# GPRSshield_v1_4.net
KiCad netlist of a schematic drawn in EAGLE
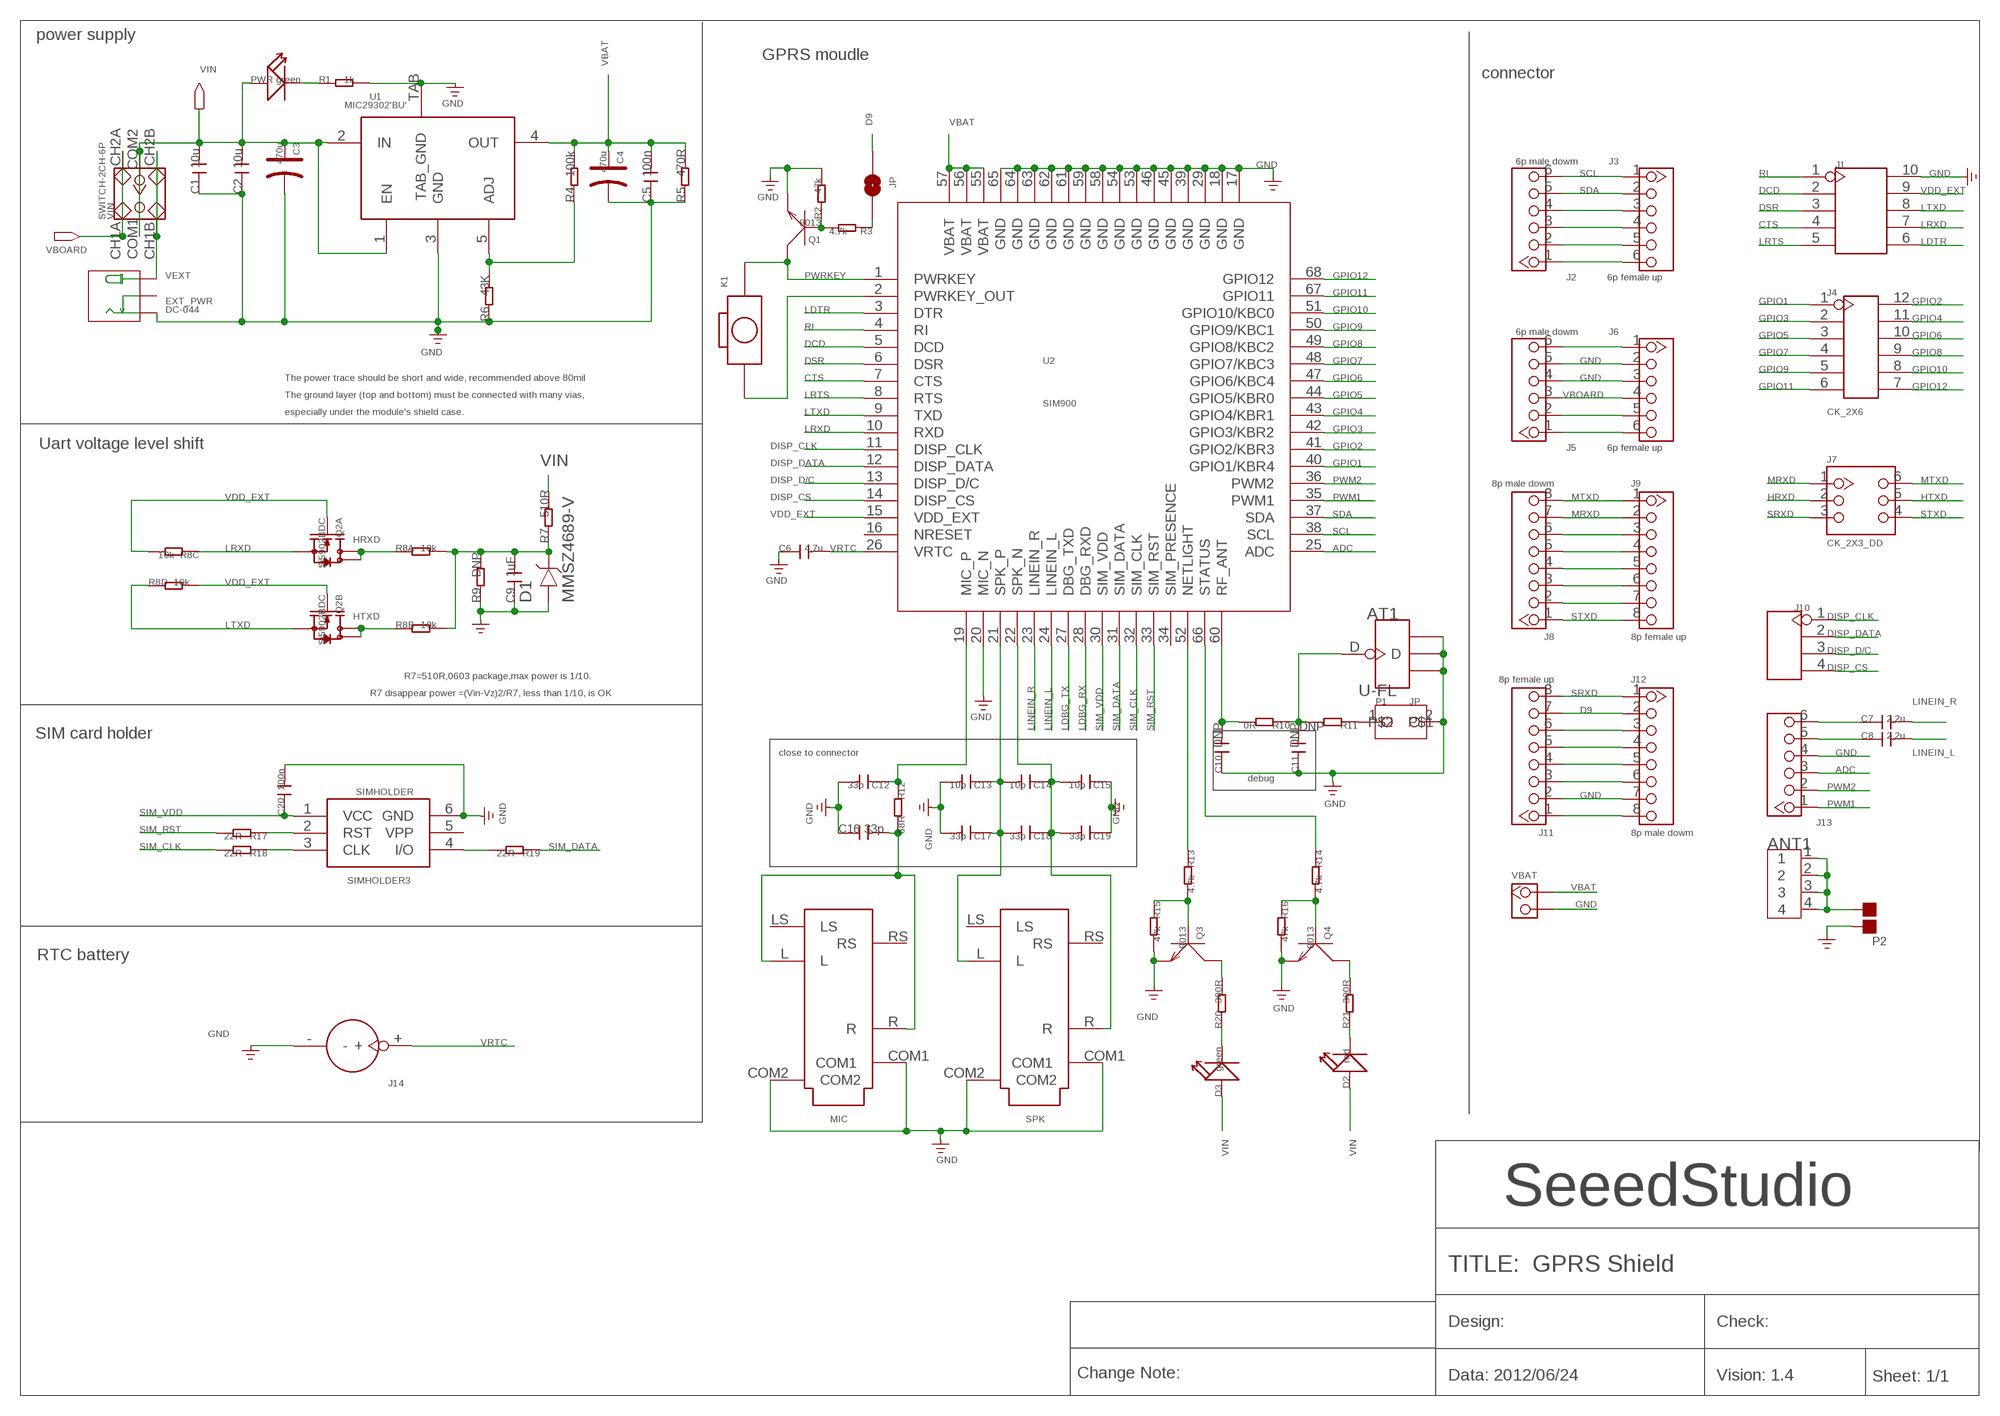
[diagram p0: schematic, sheet 1]

(export (version "E")
  (design (tool "Eeschema 10.0.6"))
  (components
    (comp (ref "ANT1")
      (value "ANTENNA-SMA-IPX")
      (footprint "eagle-import:SMA-TO-IPX")
      (libsource (lib "eagle-import") (part "ANTENNA-SMA-IPX"))
    )
    (comp (ref "AT1")
      (value "U-FL")
      (footprint "eagle-import:4P-U-FL")
      (libsource (lib "eagle-import") (part "ANTENNA-U-FL"))
    )
    (comp (ref "C1")
      (value "10u")
      (footprint "eagle-import:0603")
      (libsource (lib "eagle-import") (part "C-0603"))
    )
    (comp (ref "C2")
      (value "10u")
      (footprint "eagle-import:0603")
      (libsource (lib "eagle-import") (part "C-0603"))
    )
    (comp (ref "C3")
      (value "470u")
      (footprint "eagle-import:AVX_D")
      (libsource (lib "eagle-import") (part "006-CAP_AVX_D"))
    )
    (comp (ref "C4")
      (value "470u")
      (footprint "eagle-import:AVX_D")
      (libsource (lib "eagle-import") (part "006-CAP_AVX_D"))
    )
    (comp (ref "C5")
      (value "100n")
      (footprint "eagle-import:0603")
      (libsource (lib "eagle-import") (part "C-0603"))
    )
    (comp (ref "C6")
      (value "4.7u")
      (footprint "eagle-import:0805")
      (libsource (lib "eagle-import") (part "C-0805"))
    )
    (comp (ref "C7")
      (value "2.2u")
      (footprint "eagle-import:0603")
      (libsource (lib "eagle-import") (part "C-0603"))
    )
    (comp (ref "C8")
      (value "2.2u")
      (footprint "eagle-import:0603")
      (libsource (lib "eagle-import") (part "C-0603"))
    )
    (comp (ref "C9")
      (value "1uF")
      (footprint "eagle-import:0603")
      (libsource (lib "eagle-import") (part "C-0603"))
    )
    (comp (ref "C10")
      (value "DNP")
      (footprint "eagle-import:0402")
      (libsource (lib "eagle-import") (part "C-0402"))
    )
    (comp (ref "C11")
      (value "DNP")
      (footprint "eagle-import:0402")
      (libsource (lib "eagle-import") (part "C-0402"))
    )
    (comp (ref "C12")
      (value "33p")
      (footprint "eagle-import:0603")
      (libsource (lib "eagle-import") (part "C-0603"))
    )
    (comp (ref "C13")
      (value "10p")
      (footprint "eagle-import:0402")
      (libsource (lib "eagle-import") (part "C-0402"))
    )
    (comp (ref "C14")
      (value "10p")
      (footprint "eagle-import:0402")
      (libsource (lib "eagle-import") (part "C-0402"))
    )
    (comp (ref "C15")
      (value "10p")
      (footprint "eagle-import:0402")
      (libsource (lib "eagle-import") (part "C-0402"))
    )
    (comp (ref "C16")
      (value "33p")
      (footprint "eagle-import:0603")
      (libsource (lib "eagle-import") (part "C-0603"))
    )
    (comp (ref "C17")
      (value "33p")
      (footprint "eagle-import:0402")
      (libsource (lib "eagle-import") (part "C-0402"))
    )
    (comp (ref "C18")
      (value "33p")
      (footprint "eagle-import:0402")
      (libsource (lib "eagle-import") (part "C-0402"))
    )
    (comp (ref "C19")
      (value "33p")
      (footprint "eagle-import:0402")
      (libsource (lib "eagle-import") (part "C-0402"))
    )
    (comp (ref "C20")
      (value "100n")
      (footprint "eagle-import:0603")
      (libsource (lib "eagle-import") (part "C-0603"))
    )
    (comp (ref "D1")
      (value "MMSZ4689-V")
      (footprint "eagle-import:SOD123-2.7X1.6")
      (libsource (lib "eagle-import") (part "D-VOL'MMSZ4681'"))
    )
    (comp (ref "D2")
      (value "red")
      (footprint "eagle-import:LED-0603")
      (libsource (lib "eagle-import") (part "LED'0603'"))
    )
    (comp (ref "D3")
      (value "green")
      (footprint "eagle-import:LED-0603")
      (libsource (lib "eagle-import") (part "LED'0603'"))
    )
    (comp (ref "EXT_PWR")
      (value "DC-044")
      (footprint "eagle-import:DC-404")
      (libsource (lib "eagle-import") (part "DC-044"))
    )
    (comp (ref "J1")
      (value "HEADER-2X5P-2.54")
      (footprint "eagle-import:2X5P-2.54")
      (libsource (lib "eagle-import") (part "HEADER-2X5P-2.54"))
    )
    (comp (ref "J2")
      (value "6p male dowm")
      (footprint "eagle-import:CK_1X6")
      (libsource (lib "eagle-import") (part "HEADER_1X6"))
    )
    (comp (ref "J3")
      (value "6p female up")
      (footprint "eagle-import:CK_1X6")
      (libsource (lib "eagle-import") (part "HEADER_1X6"))
    )
    (comp (ref "J4")
      (value "CK_2X6")
      (footprint "eagle-import:CK_2X6")
      (libsource (lib "eagle-import") (part "CK_2X6"))
    )
    (comp (ref "J5")
      (value "6p male dowm")
      (footprint "eagle-import:CK_1X6")
      (libsource (lib "eagle-import") (part "HEADER_1X6"))
    )
    (comp (ref "J6")
      (value "6p female up")
      (footprint "eagle-import:CK_1X6")
      (libsource (lib "eagle-import") (part "HEADER_1X6"))
    )
    (comp (ref "J7")
      (value "CK_2X3_DD")
      (footprint "eagle-import:CK_2X3")
      (libsource (lib "eagle-import") (part "CK_2X3_DD"))
    )
    (comp (ref "J8")
      (value "8p male dowm")
      (footprint "eagle-import:CK_1X8")
      (libsource (lib "eagle-import") (part "CK_1X8DD"))
    )
    (comp (ref "J9")
      (value "8p female up")
      (footprint "eagle-import:CK_1X8")
      (libsource (lib "eagle-import") (part "CK_1X8DD"))
    )
    (comp (ref "J10")
      (value "HEADER-4P'2.54-90D-FEMALE'")
      (footprint "eagle-import:4P-2.54-90D-FEMALE")
      (libsource (lib "eagle-import") (part "HEADER-4P'2.54-90D-FEMALE'"))
    )
    (comp (ref "J11")
      (value "8p female up")
      (footprint "eagle-import:CK_1X8")
      (libsource (lib "eagle-import") (part "CK_1X8DD"))
    )
    (comp (ref "J12")
      (value "8p male dowm")
      (footprint "eagle-import:CK_1X8")
      (libsource (lib "eagle-import") (part "CK_1X8DD"))
    )
    (comp (ref "J13")
      (value "HEADER_1X6")
      (footprint "eagle-import:CK_1X6")
      (libsource (lib "eagle-import") (part "HEADER_1X6"))
    )
    (comp (ref "J14")
      (value "HOLDER-BATTERY-2P-CR1220")
      (footprint "eagle-import:CR1220")
      (libsource (lib "eagle-import") (part "HOLDER-BATTERY-2P-CR1220"))
    )
    (comp (ref "JP")
      (value "PAD-SOLDERJUMPERNC")
      (footprint "eagle-import:2P-SMD-3.3X2")
      (libsource (lib "eagle-import") (part "PAD-SOLDERJUMPERNC"))
    )
    (comp (ref "K1")
      (value "BOTTON_1_DP")
      (footprint "eagle-import:BTN_5.0_RST")
      (libsource (lib "eagle-import") (part "BOTTON_1_DP"))
    )
    (comp (ref "MIC")
      (value "AUDIO-SMT")
      (footprint "eagle-import:3.5-SMD")
      (libsource (lib "eagle-import") (part "AUDIO-SMT"))
    )
    (comp (ref "P1") (value "JP") (footprint "eagle-import:JP") (libsource (lib "eagle-import") (part "JP")))
    (comp (ref "P2")
      (value "PAD-JUMPER-2P")
      (footprint "eagle-import:2P-SMD-1.78X1.27")
      (fields (field (name "PARTNO") "DNP"))
      (libsource (lib "eagle-import") (part "PAD-JUMPER-2P"))
    )
    (comp (ref "PWR")
      (value "green")
      (footprint "eagle-import:D0603")
      (libsource (lib "eagle-import") (part "007-LED0603"))
    )
    (comp (ref "Q1")
      (value "9013")
      (footprint "eagle-import:SOT23")
      (libsource (lib "eagle-import") (part "TRANSISTOR-NPN-SOT23"))
    )
    (comp (ref "Q2")
      (value "Si5902BDC")
      (footprint "eagle-import:1206-8")
      (libsource (lib "eagle-import") (part "010-DUAL-N-MOSFET_1206-8"))
    )
    (comp (ref "Q3")
      (value "9013")
      (footprint "eagle-import:SOT23")
      (libsource (lib "eagle-import") (part "TRANSISTOR-NPN-SOT23"))
    )
    (comp (ref "Q4")
      (value "9013")
      (footprint "eagle-import:SOT23")
      (libsource (lib "eagle-import") (part "TRANSISTOR-NPN-SOT23"))
    )
    (comp (ref "R1")
      (value "1k")
      (footprint "eagle-import:0603")
      (libsource (lib "eagle-import") (part "R-0603"))
    )
    (comp (ref "R2")
      (value "47k")
      (footprint "eagle-import:0603")
      (libsource (lib "eagle-import") (part "R-0603"))
    )
    (comp (ref "R3")
      (value "4.7k")
      (footprint "eagle-import:0603")
      (libsource (lib "eagle-import") (part "R-0603"))
    )
    (comp (ref "R4")
      (value "100k")
      (footprint "eagle-import:0603")
      (libsource (lib "eagle-import") (part "R-0603"))
    )
    (comp (ref "R5")
      (value "470R")
      (footprint "eagle-import:0603")
      (libsource (lib "eagle-import") (part "R-0603"))
    )
    (comp (ref "R6")
      (value "43K")
      (footprint "eagle-import:0603")
      (libsource (lib "eagle-import") (part "R-0603"))
    )
    (comp (ref "R7")
      (value "510R")
      (footprint "eagle-import:0603")
      (libsource (lib "eagle-import") (part "R-0603"))
    )
    (comp (ref "R8")
      (value "10k")
      (footprint "eagle-import:1206-8-3.3X2.4")
      (libsource (lib "eagle-import") (part "R-4R-1206"))
    )
    (comp (ref "R9")
      (value "DNP")
      (footprint "eagle-import:0603")
      (libsource (lib "eagle-import") (part "R-0603"))
    )
    (comp (ref "R10")
      (value "0R")
      (footprint "eagle-import:0402")
      (libsource (lib "eagle-import") (part "R-0402"))
    )
    (comp (ref "R11")
      (value "DNP")
      (footprint "eagle-import:0402")
      (libsource (lib "eagle-import") (part "R-0402"))
    )
    (comp (ref "R12")
      (value "68R")
      (footprint "eagle-import:0603")
      (libsource (lib "eagle-import") (part "R-0603"))
    )
    (comp (ref "R13")
      (value "4.7k")
      (footprint "eagle-import:0603")
      (libsource (lib "eagle-import") (part "R-0603"))
    )
    (comp (ref "R14")
      (value "4.7k")
      (footprint "eagle-import:0603")
      (libsource (lib "eagle-import") (part "R-0603"))
    )
    (comp (ref "R15")
      (value "47k")
      (footprint "eagle-import:0603")
      (libsource (lib "eagle-import") (part "R-0603"))
    )
    (comp (ref "R16")
      (value "47k")
      (footprint "eagle-import:0603")
      (libsource (lib "eagle-import") (part "R-0603"))
    )
    (comp (ref "R17")
      (value "22R")
      (footprint "eagle-import:0603")
      (libsource (lib "eagle-import") (part "R-0603"))
    )
    (comp (ref "R18")
      (value "22R")
      (footprint "eagle-import:0603")
      (libsource (lib "eagle-import") (part "R-0603"))
    )
    (comp (ref "R19")
      (value "22R")
      (footprint "eagle-import:0603")
      (libsource (lib "eagle-import") (part "R-0603"))
    )
    (comp (ref "R20")
      (value "300R")
      (footprint "eagle-import:0603")
      (libsource (lib "eagle-import") (part "R-0603"))
    )
    (comp (ref "R21")
      (value "300R")
      (footprint "eagle-import:0603")
      (libsource (lib "eagle-import") (part "R-0603"))
    )
    (comp (ref "SIMHOLDER")
      (value "SIMHOLDER3")
      (footprint "eagle-import:SIMHOLDER3")
      (libsource (lib "eagle-import") (part "SIMHOLDER3"))
    )
    (comp (ref "SPK")
      (value "AUDIO-SMT")
      (footprint "eagle-import:3.5-SMD")
      (libsource (lib "eagle-import") (part "AUDIO-SMT"))
    )
    (comp (ref "U1")
      (value "MIC29302'BU'")
      (footprint "eagle-import:TO-263")
      (libsource (lib "eagle-import") (part "MIC29302'BU'"))
    )
    (comp (ref "U2")
      (value "SIM900")
      (footprint "eagle-import:SIM900")
      (libsource (lib "eagle-import") (part "SIM900"))
    )
    (comp (ref "VBAT")
      (value "DNP")
      (footprint "eagle-import:CK_1_2")
      (libsource (lib "eagle-import") (part "HEADER_1X2_2.54"))
    )
    (comp (ref "VIN")
      (value "SWITCH-2CH-6P")
      (footprint "eagle-import:6P-2CH-2.54-7.6X3.0")
      (libsource (lib "eagle-import") (part "SWITCH-2CH-6P"))
    )
  )
  (nets
    (net (code "1") (name "/ADC") (class "Default")
      (node (ref "J13") (pin "3") (pinfunction "3_3") (pintype "bidirectional"))
      (node (ref "U2") (pin "25") (pinfunction "ADC_25") (pintype "input"))
    )
    (net (code "2") (name "/CTS") (class "Default")
      (node (ref "J1") (pin "4") (pinfunction "4_4") (pintype "bidirectional"))
      (node (ref "U2") (pin "7") (pinfunction "CTS_7") (pintype "output"))
    )
    (net (code "3") (name "/D9") (class "Default")
      (node (ref "J11") (pin "7") (pinfunction "P$7_7") (pintype "bidirectional"))
      (node (ref "J12") (pin "2") (pinfunction "P$2_2") (pintype "bidirectional"))
      (node (ref "JP") (pin "1") (pinfunction "1_1") (pintype "passive"))
    )
    (net (code "4") (name "/DCD") (class "Default")
      (node (ref "J1") (pin "2") (pinfunction "2_2") (pintype "bidirectional"))
      (node (ref "U2") (pin "5") (pinfunction "DCD_5") (pintype "output"))
    )
    (net (code "5") (name "/DISP_CLK") (class "Default")
      (node (ref "J10") (pin "1") (pinfunction "P$1_1") (pintype "bidirectional"))
      (node (ref "U2") (pin "11") (pinfunction "DISP_CLK_11") (pintype "output"))
    )
    (net (code "6") (name "/DISP_CS") (class "Default")
      (node (ref "J10") (pin "4") (pinfunction "P$4_4") (pintype "bidirectional"))
      (node (ref "U2") (pin "14") (pinfunction "DISP_CS_14") (pintype "output"))
    )
    (net (code "7") (name "/DISP_DATA") (class "Default")
      (node (ref "J10") (pin "2") (pinfunction "P$2_2") (pintype "bidirectional"))
      (node (ref "U2") (pin "12") (pinfunction "DISP_DATA_12") (pintype "bidirectional"))
    )
    (net (code "8") (name "/DISP_D{slash}C") (class "Default")
      (node (ref "J10") (pin "3") (pinfunction "P$3_3") (pintype "bidirectional"))
      (node (ref "U2") (pin "13") (pinfunction "DISP_D/C_13") (pintype "output"))
    )
    (net (code "9") (name "/DSR") (class "Default")
      (node (ref "J1") (pin "3") (pinfunction "3_3") (pintype "bidirectional"))
      (node (ref "U2") (pin "6") (pinfunction "DSR_6") (pintype "output"))
    )
    (net (code "10") (name "/GPIO1") (class "Default")
      (node (ref "J4") (pin "1") (pinfunction "1_1") (pintype "bidirectional"))
      (node (ref "U2") (pin "40") (pinfunction "GPIO1/KBR4_40") (pintype "output"))
    )
    (net (code "11") (name "/GPIO2") (class "Default")
      (node (ref "J4") (pin "12") (pinfunction "12_12") (pintype "bidirectional"))
      (node (ref "U2") (pin "41") (pinfunction "GPIO2/KBR3_41") (pintype "output"))
    )
    (net (code "12") (name "/GPIO3") (class "Default")
      (node (ref "J4") (pin "2") (pinfunction "2_2") (pintype "bidirectional"))
      (node (ref "U2") (pin "42") (pinfunction "GPIO3/KBR2_42") (pintype "output"))
    )
    (net (code "13") (name "/GPIO4") (class "Default")
      (node (ref "J4") (pin "11") (pinfunction "11_11") (pintype "bidirectional"))
      (node (ref "U2") (pin "43") (pinfunction "GPIO4/KBR1_43") (pintype "output"))
    )
    (net (code "14") (name "/GPIO5") (class "Default")
      (node (ref "J4") (pin "3") (pinfunction "3_3") (pintype "bidirectional"))
      (node (ref "U2") (pin "44") (pinfunction "GPIO5/KBR0_44") (pintype "output"))
    )
    (net (code "15") (name "/GPIO6") (class "Default")
      (node (ref "J4") (pin "10") (pinfunction "10_10") (pintype "bidirectional"))
      (node (ref "U2") (pin "47") (pinfunction "GPIO6/KBC4_47") (pintype "input"))
    )
    (net (code "16") (name "/GPIO7") (class "Default")
      (node (ref "J4") (pin "4") (pinfunction "4_4") (pintype "bidirectional"))
      (node (ref "U2") (pin "48") (pinfunction "GPIO7/KBC3_48") (pintype "bidirectional"))
    )
    (net (code "17") (name "/GPIO8") (class "Default")
      (node (ref "J4") (pin "9") (pinfunction "9_9") (pintype "bidirectional"))
      (node (ref "U2") (pin "49") (pinfunction "GPIO8/KBC2_49") (pintype "input"))
    )
    (net (code "18") (name "/GPIO9") (class "Default")
      (node (ref "J4") (pin "5") (pinfunction "5_5") (pintype "bidirectional"))
      (node (ref "U2") (pin "50") (pinfunction "GPIO9/KBC1_50") (pintype "input"))
    )
    (net (code "19") (name "/GPIO10") (class "Default")
      (node (ref "J4") (pin "8") (pinfunction "8_8") (pintype "bidirectional"))
      (node (ref "U2") (pin "51") (pinfunction "GPIO10/KBC0_51") (pintype "bidirectional"))
    )
    (net (code "20") (name "/GPIO11") (class "Default")
      (node (ref "J4") (pin "6") (pinfunction "6_6") (pintype "bidirectional"))
      (node (ref "U2") (pin "67") (pinfunction "GPIO11_67") (pintype "bidirectional"))
    )
    (net (code "21") (name "/GPIO12") (class "Default")
      (node (ref "J4") (pin "7") (pinfunction "7_7") (pintype "bidirectional"))
      (node (ref "U2") (pin "68") (pinfunction "GPIO12_68") (pintype "bidirectional"))
    )
    (net (code "22") (name "/HRXD") (class "Default")
      (node (ref "J7") (pin "2") (pinfunction "2_2") (pintype "bidirectional"))
      (node (ref "Q2") (pin "7") (pinfunction "D_7") (pintype "passive"))
      (node (ref "Q2") (pin "8") (pinfunction "D_8") (pintype "passive"))
      (node (ref "R8") (pin "1") (pinfunction "1_1") (pintype "passive"))
    )
    (net (code "23") (name "/HTXD") (class "Default")
      (node (ref "J7") (pin "5") (pinfunction "5_5") (pintype "bidirectional"))
      (node (ref "Q2") (pin "5") (pinfunction "D_5") (pintype "passive"))
      (node (ref "Q2") (pin "6") (pinfunction "D_6") (pintype "passive"))
      (node (ref "R8") (pin "2") (pinfunction "1_2") (pintype "passive"))
    )
    (net (code "24") (name "/LDBG_RX") (class "Default")
      (node (ref "U2") (pin "28") (pinfunction "DBG_RXD_28") (pintype "input"))
    )
    (net (code "25") (name "/LDBG_TX") (class "Default")
      (node (ref "U2") (pin "27") (pinfunction "DBG_TXD_27") (pintype "output"))
    )
    (net (code "26") (name "/LDTR") (class "Default")
      (node (ref "J1") (pin "6") (pinfunction "6_6") (pintype "bidirectional"))
      (node (ref "U2") (pin "3") (pinfunction "DTR_3") (pintype "input"))
    )
    (net (code "27") (name "/LINEIN_L") (class "Default")
      (node (ref "C8") (pin "2") (pinfunction "2_2") (pintype "passive"))
      (node (ref "U2") (pin "24") (pinfunction "LINEIN_L_24") (pintype "input"))
    )
    (net (code "28") (name "/LINEIN_R") (class "Default")
      (node (ref "C7") (pin "2") (pinfunction "2_2") (pintype "passive"))
      (node (ref "U2") (pin "23") (pinfunction "LINEIN_R_23") (pintype "input"))
    )
    (net (code "29") (name "/LRTS") (class "Default")
      (node (ref "J1") (pin "5") (pinfunction "5_5") (pintype "bidirectional"))
      (node (ref "U2") (pin "8") (pinfunction "RTS_8") (pintype "input"))
    )
    (net (code "30") (name "/LRXD") (class "Default")
      (node (ref "J1") (pin "7") (pinfunction "7_7") (pintype "bidirectional"))
      (node (ref "Q2") (pin "1") (pinfunction "S_1") (pintype "passive"))
      (node (ref "R8") (pin "3") (pinfunction "1_3") (pintype "passive"))
      (node (ref "U2") (pin "10") (pinfunction "RXD_10") (pintype "input"))
    )
    (net (code "31") (name "/LTXD") (class "Default")
      (node (ref "J1") (pin "8") (pinfunction "8_8") (pintype "bidirectional"))
      (node (ref "Q2") (pin "3") (pinfunction "S_3") (pintype "passive"))
      (node (ref "R8") (pin "4") (pinfunction "1_4") (pintype "passive"))
      (node (ref "U2") (pin "9") (pinfunction "TXD_9") (pintype "output"))
    )
    (net (code "32") (name "/MRXD") (class "Default")
      (node (ref "J7") (pin "1") (pinfunction "1_1") (pintype "bidirectional"))
      (node (ref "J8") (pin "7") (pinfunction "P$7_7") (pintype "bidirectional"))
      (node (ref "J9") (pin "2") (pinfunction "P$2_2") (pintype "bidirectional"))
    )
    (net (code "33") (name "/MTXD") (class "Default")
      (node (ref "J7") (pin "6") (pinfunction "6_6") (pintype "bidirectional"))
      (node (ref "J8") (pin "8") (pinfunction "P$8_8") (pintype "bidirectional"))
      (node (ref "J9") (pin "1") (pinfunction "P$1_1") (pintype "bidirectional"))
    )
    (net (code "34") (name "/PWM1") (class "Default")
      (node (ref "J13") (pin "1") (pinfunction "1_1") (pintype "bidirectional"))
      (node (ref "U2") (pin "35") (pinfunction "PWM1_35") (pintype "output"))
    )
    (net (code "35") (name "/PWM2") (class "Default")
      (node (ref "J13") (pin "2") (pinfunction "2_2") (pintype "bidirectional"))
      (node (ref "U2") (pin "36") (pinfunction "PWM2_36") (pintype "output"))
    )
    (net (code "36") (name "/PWRKEY") (class "Default")
      (node (ref "K1") (pin "P$2") (pinfunction "2_P$2") (pintype "bidirectional"))
      (node (ref "Q1") (pin "3") (pinfunction "C_3") (pintype "passive"))
      (node (ref "U2") (pin "1") (pinfunction "PWRKEY_1") (pintype "input"))
    )
    (net (code "37") (name "/RI") (class "Default")
      (node (ref "J1") (pin "1") (pinfunction "1_1") (pintype "bidirectional"))
      (node (ref "U2") (pin "4") (pinfunction "RI_4") (pintype "output"))
    )
    (net (code "38") (name "/SCL") (class "Default")
      (node (ref "J2") (pin "6") (pinfunction "6_6") (pintype "bidirectional"))
      (node (ref "J3") (pin "1") (pinfunction "1_1") (pintype "bidirectional"))
      (node (ref "U2") (pin "38") (pinfunction "SCL_38") (pintype "output"))
    )
    (net (code "39") (name "/SDA") (class "Default")
      (node (ref "J2") (pin "5") (pinfunction "5_5") (pintype "bidirectional"))
      (node (ref "J3") (pin "2") (pinfunction "2_2") (pintype "bidirectional"))
      (node (ref "U2") (pin "37") (pinfunction "SDA_37") (pintype "bidirectional"))
    )
    (net (code "40") (name "/SIM_CLK") (class "Default")
      (node (ref "R18") (pin "2") (pinfunction "2_2") (pintype "passive"))
      (node (ref "U2") (pin "32") (pinfunction "SIM_CLK_32") (pintype "output"))
    )
    (net (code "41") (name "/SIM_DATA") (class "Default")
      (node (ref "R19") (pin "1") (pinfunction "1_1") (pintype "passive"))
      (node (ref "U2") (pin "31") (pinfunction "SIM_DATA_31") (pintype "bidirectional"))
    )
    (net (code "42") (name "/SIM_RST") (class "Default")
      (node (ref "R17") (pin "2") (pinfunction "2_2") (pintype "passive"))
      (node (ref "U2") (pin "33") (pinfunction "SIM_RST_33") (pintype "output"))
    )
    (net (code "43") (name "/SIM_VDD") (class "Default")
      (node (ref "C20") (pin "1") (pinfunction "1_1") (pintype "passive"))
      (node (ref "SIMHOLDER") (pin "1") (pinfunction "VCC_1") (pintype "bidirectional"))
      (node (ref "U2") (pin "30") (pinfunction "SIM_VDD_30") (pintype "output"))
    )
    (net (code "44") (name "/SRXD") (class "Default")
      (node (ref "J11") (pin "8") (pinfunction "P$8_8") (pintype "bidirectional"))
      (node (ref "J12") (pin "1") (pinfunction "P$1_1") (pintype "bidirectional"))
      (node (ref "J7") (pin "3") (pinfunction "3_3") (pintype "bidirectional"))
    )
    (net (code "45") (name "/STXD") (class "Default")
      (node (ref "J7") (pin "4") (pinfunction "4_4") (pintype "bidirectional"))
      (node (ref "J8") (pin "1") (pinfunction "P$1_1") (pintype "bidirectional"))
      (node (ref "J9") (pin "8") (pinfunction "P$8_8") (pintype "bidirectional"))
    )
    (net (code "46") (name "/VBAT") (class "Default")
      (node (ref "C4") (pin "+") (pinfunction "+_+") (pintype "passive"))
      (node (ref "C5") (pin "2") (pinfunction "2_2") (pintype "passive"))
      (node (ref "R4") (pin "2") (pinfunction "2_2") (pintype "passive"))
      (node (ref "R5") (pin "2") (pinfunction "2_2") (pintype "passive"))
      (node (ref "U1") (pin "4") (pinfunction "OUT_4") (pintype "bidirectional"))
      (node (ref "U2") (pin "55") (pinfunction "VBAT_55") (pintype "power_in"))
      (node (ref "U2") (pin "56") (pinfunction "VBAT_56") (pintype "power_in"))
      (node (ref "U2") (pin "57") (pinfunction "VBAT_57") (pintype "power_in"))
      (node (ref "VBAT") (pin "1") (pinfunction "1_1") (pintype "bidirectional"))
    )
    (net (code "47") (name "/VBOARD") (class "Default")
      (node (ref "J5") (pin "3") (pinfunction "3_3") (pintype "bidirectional"))
      (node (ref "J6") (pin "4") (pinfunction "4_4") (pintype "bidirectional"))
      (node (ref "VIN") (pin "CH1A") (pinfunction "CH1A_CH1A") (pintype "bidirectional"))
      (node (ref "VIN") (pin "CH2A") (pinfunction "CH2A_CH2A") (pintype "bidirectional"))
    )
    (net (code "48") (name "/VDD_EXT") (class "Default")
      (node (ref "J1") (pin "9") (pinfunction "9_9") (pintype "bidirectional"))
      (node (ref "Q2") (pin "2") (pinfunction "G_2") (pintype "passive"))
      (node (ref "Q2") (pin "4") (pinfunction "G_4") (pintype "passive"))
      (node (ref "R8") (pin "5") (pinfunction "2_5") (pintype "passive"))
      (node (ref "R8") (pin "6") (pinfunction "2_6") (pintype "passive"))
      (node (ref "U2") (pin "15") (pinfunction "VDD_EXT_15") (pintype "output"))
    )
    (net (code "49") (name "/VEXT") (class "Default")
      (node (ref "EXT_PWR") (pin "+") (pinfunction "+_+") (pintype "bidirectional"))
      (node (ref "VIN") (pin "CH1B") (pinfunction "CH1B_CH1B") (pintype "bidirectional"))
      (node (ref "VIN") (pin "CH2B") (pinfunction "CH2B_CH2B") (pintype "bidirectional"))
    )
    (net (code "50") (name "/VIN") (class "Default")
      (node (ref "C1") (pin "2") (pinfunction "2_2") (pintype "passive"))
      (node (ref "C2") (pin "2") (pinfunction "2_2") (pintype "passive"))
      (node (ref "C3") (pin "+") (pinfunction "+_+") (pintype "passive"))
      (node (ref "D2") (pin "+") (pinfunction "+_+") (pintype "passive"))
      (node (ref "D3") (pin "+") (pinfunction "+_+") (pintype "passive"))
      (node (ref "PWR") (pin "+") (pinfunction "+_+") (pintype "passive"))
      (node (ref "R7") (pin "2") (pinfunction "2_2") (pintype "passive"))
      (node (ref "U1") (pin "1") (pinfunction "EN_1") (pintype "bidirectional"))
      (node (ref "U1") (pin "2") (pinfunction "IN_2") (pintype "bidirectional"))
      (node (ref "VIN") (pin "COM1") (pinfunction "COM1_COM1") (pintype "bidirectional"))
      (node (ref "VIN") (pin "COM2") (pinfunction "COM2_COM2") (pintype "bidirectional"))
    )
    (net (code "51") (name "/VRTC") (class "Default")
      (node (ref "C6") (pin "2") (pinfunction "2_2") (pintype "passive"))
      (node (ref "J14") (pin "+") (pinfunction "+_+") (pintype "bidirectional"))
      (node (ref "U2") (pin "26") (pinfunction "VRTC_26") (pintype "bidirectional"))
    )
    (net (code "52") (name "GND_POWER") (class "Default")
      (node (ref "AT1") (pin "GND1") (pinfunction "GND1_GND1") (pintype "bidirectional"))
      (node (ref "AT1") (pin "GND2") (pinfunction "GND2_GND2") (pintype "bidirectional"))
      (node (ref "AT1") (pin "GND3") (pinfunction "GND3_GND3") (pintype "bidirectional"))
      (node (ref "C1") (pin "1") (pinfunction "1_1") (pintype "passive"))
      (node (ref "C10") (pin "1") (pinfunction "1_1") (pintype "passive"))
      (node (ref "C11") (pin "1") (pinfunction "1_1") (pintype "passive"))
      (node (ref "C12") (pin "2") (pinfunction "2_2") (pintype "passive"))
      (node (ref "C13") (pin "2") (pinfunction "2_2") (pintype "passive"))
      (node (ref "C15") (pin "1") (pinfunction "1_1") (pintype "passive"))
      (node (ref "C16") (pin "1") (pinfunction "1_1") (pintype "passive"))
      (node (ref "C17") (pin "2") (pinfunction "2_2") (pintype "passive"))
      (node (ref "C19") (pin "1") (pinfunction "1_1") (pintype "passive"))
      (node (ref "C2") (pin "1") (pinfunction "1_1") (pintype "passive"))
      (node (ref "C20") (pin "2") (pinfunction "2_2") (pintype "passive"))
      (node (ref "C3") (pin "-") (pinfunction "-_-") (pintype "passive"))
      (node (ref "C4") (pin "-") (pinfunction "-_-") (pintype "passive"))
      (node (ref "C5") (pin "1") (pinfunction "1_1") (pintype "passive"))
      (node (ref "C6") (pin "1") (pinfunction "1_1") (pintype "passive"))
      (node (ref "C9") (pin "1") (pinfunction "1_1") (pintype "passive"))
      (node (ref "D1") (pin "1") (pinfunction "1_1") (pintype "bidirectional"))
      (node (ref "EXT_PWR") (pin "-") (pinfunction "-_-") (pintype "bidirectional"))
      (node (ref "J1") (pin "10") (pinfunction "10_10") (pintype "bidirectional"))
      (node (ref "J11") (pin "2") (pinfunction "P$2_2") (pintype "bidirectional"))
      (node (ref "J12") (pin "7") (pinfunction "P$7_7") (pintype "bidirectional"))
      (node (ref "J13") (pin "4") (pinfunction "4_4") (pintype "bidirectional"))
      (node (ref "J14") (pin "-") (pinfunction "-_-") (pintype "bidirectional"))
      (node (ref "J5") (pin "4") (pinfunction "4_4") (pintype "bidirectional"))
      (node (ref "J5") (pin "5") (pinfunction "5_5") (pintype "bidirectional"))
      (node (ref "J6") (pin "2") (pinfunction "2_2") (pintype "bidirectional"))
      (node (ref "J6") (pin "3") (pinfunction "3_3") (pintype "bidirectional"))
      (node (ref "MIC") (pin "COM1") (pinfunction "COM1_COM1") (pintype "bidirectional"))
      (node (ref "MIC") (pin "COM2") (pinfunction "COM2_COM2") (pintype "bidirectional"))
      (node (ref "P1") (pin "2") (pinfunction "P$2_2") (pintype "bidirectional"))
      (node (ref "P2") (pin "2") (pinfunction "2_2") (pintype "bidirectional"))
      (node (ref "Q1") (pin "2") (pinfunction "E_2") (pintype "passive"))
      (node (ref "Q3") (pin "2") (pinfunction "E_2") (pintype "passive"))
      (node (ref "Q4") (pin "2") (pinfunction "E_2") (pintype "passive"))
      (node (ref "R1") (pin "2") (pinfunction "2_2") (pintype "passive"))
      (node (ref "R15") (pin "2") (pinfunction "2_2") (pintype "passive"))
      (node (ref "R16") (pin "2") (pinfunction "2_2") (pintype "passive"))
      (node (ref "R2") (pin "2") (pinfunction "2_2") (pintype "passive"))
      (node (ref "R5") (pin "1") (pinfunction "1_1") (pintype "passive"))
      (node (ref "R6") (pin "1") (pinfunction "1_1") (pintype "passive"))
      (node (ref "R9") (pin "1") (pinfunction "1_1") (pintype "passive"))
      (node (ref "SIMHOLDER") (pin "6") (pinfunction "GND_6") (pintype "bidirectional"))
      (node (ref "SPK") (pin "COM1") (pinfunction "COM1_COM1") (pintype "bidirectional"))
      (node (ref "SPK") (pin "COM2") (pinfunction "COM2_COM2") (pintype "bidirectional"))
      (node (ref "U1") (pin "3") (pinfunction "GND_3") (pintype "bidirectional"))
      (node (ref "U1") (pin "TAB") (pinfunction "TAB_GND_TAB") (pintype "bidirectional"))
      (node (ref "U2") (pin "17") (pinfunction "GND_17") (pintype "power_in"))
      (node (ref "U2") (pin "18") (pinfunction "GND_18") (pintype "power_in"))
      (node (ref "U2") (pin "20") (pinfunction "MIC_N_20") (pintype "input"))
      (node (ref "U2") (pin "29") (pinfunction "GND_29") (pintype "power_in"))
      (node (ref "U2") (pin "39") (pinfunction "GND_39") (pintype "power_in"))
      (node (ref "U2") (pin "45") (pinfunction "GND_45") (pintype "power_in"))
      (node (ref "U2") (pin "46") (pinfunction "GND_46") (pintype "power_in"))
      (node (ref "U2") (pin "53") (pinfunction "GND_53") (pintype "power_in"))
      (node (ref "U2") (pin "54") (pinfunction "GND_54") (pintype "power_in"))
      (node (ref "U2") (pin "58") (pinfunction "GND_58") (pintype "power_in"))
      (node (ref "U2") (pin "59") (pinfunction "GND_59") (pintype "power_in"))
      (node (ref "U2") (pin "61") (pinfunction "GND_61") (pintype "power_in"))
      (node (ref "U2") (pin "62") (pinfunction "GND_62") (pintype "power_in"))
      (node (ref "U2") (pin "63") (pinfunction "GND_63") (pintype "power_in"))
      (node (ref "U2") (pin "64") (pinfunction "GND_64") (pintype "power_in"))
      (node (ref "U2") (pin "65") (pinfunction "GND_65") (pintype "power_in"))
      (node (ref "VBAT") (pin "2") (pinfunction "2_2") (pintype "bidirectional"))
    )
    (net (code "53") (name "Net-(ANT1-Pad1)") (class "Default")
      (node (ref "ANT1") (pin "1") (pinfunction "1_1") (pintype "bidirectional"))
      (node (ref "ANT1") (pin "2") (pinfunction "2_2") (pintype "bidirectional"))
      (node (ref "ANT1") (pin "3") (pinfunction "3_3") (pintype "bidirectional"))
      (node (ref "ANT1") (pin "4") (pinfunction "4_4") (pintype "bidirectional"))
      (node (ref "P2") (pin "1") (pinfunction "1_1") (pintype "bidirectional"))
    )
    (net (code "54") (name "Net-(AT1-PadD)") (class "Default")
      (node (ref "AT1") (pin "D") (pinfunction "D_D") (pintype "bidirectional"))
      (node (ref "C11") (pin "2") (pinfunction "2_2") (pintype "passive"))
      (node (ref "R10") (pin "1") (pinfunction "1_1") (pintype "passive"))
      (node (ref "R11") (pin "2") (pinfunction "2_2") (pintype "passive"))
    )
    (net (code "55") (name "Net-(C7-Pad1)") (class "Default")
      (node (ref "C7") (pin "1") (pinfunction "1_1") (pintype "passive"))
      (node (ref "J13") (pin "6") (pinfunction "6_6") (pintype "bidirectional"))
    )
    (net (code "56") (name "Net-(C8-Pad1)") (class "Default")
      (node (ref "C8") (pin "1") (pinfunction "1_1") (pintype "passive"))
      (node (ref "J13") (pin "5") (pinfunction "5_5") (pintype "bidirectional"))
    )
    (net (code "57") (name "Net-(C16-Pad2)") (class "Default")
      (node (ref "C16") (pin "2") (pinfunction "2_2") (pintype "passive"))
      (node (ref "MIC") (pin "L") (pinfunction "L_L") (pintype "bidirectional"))
      (node (ref "MIC") (pin "R") (pinfunction "R_R") (pintype "bidirectional"))
      (node (ref "R12") (pin "2") (pinfunction "2_2") (pintype "passive"))
    )
    (net (code "58") (name "Net-(D2-Pad-)") (class "Default")
      (node (ref "D2") (pin "-") (pinfunction "-_-") (pintype "passive"))
      (node (ref "R21") (pin "1") (pinfunction "1_1") (pintype "passive"))
    )
    (net (code "59") (name "Net-(D3-Pad-)") (class "Default")
      (node (ref "D3") (pin "-") (pinfunction "-_-") (pintype "passive"))
      (node (ref "R20") (pin "1") (pinfunction "1_1") (pintype "passive"))
    )
    (net (code "60") (name "Net-(J2-Pad1)") (class "Default")
      (node (ref "J2") (pin "1") (pinfunction "1_1") (pintype "bidirectional"))
      (node (ref "J3") (pin "6") (pinfunction "6_6") (pintype "bidirectional"))
    )
    (net (code "61") (name "Net-(J2-Pad2)") (class "Default")
      (node (ref "J2") (pin "2") (pinfunction "2_2") (pintype "bidirectional"))
      (node (ref "J3") (pin "5") (pinfunction "5_5") (pintype "bidirectional"))
    )
    (net (code "62") (name "Net-(J2-Pad3)") (class "Default")
      (node (ref "J2") (pin "3") (pinfunction "3_3") (pintype "bidirectional"))
      (node (ref "J3") (pin "4") (pinfunction "4_4") (pintype "bidirectional"))
    )
    (net (code "63") (name "Net-(J2-Pad4)") (class "Default")
      (node (ref "J2") (pin "4") (pinfunction "4_4") (pintype "bidirectional"))
      (node (ref "J3") (pin "3") (pinfunction "3_3") (pintype "bidirectional"))
    )
    (net (code "64") (name "Net-(J5-Pad1)") (class "Default")
      (node (ref "J5") (pin "1") (pinfunction "1_1") (pintype "bidirectional"))
      (node (ref "J6") (pin "6") (pinfunction "6_6") (pintype "bidirectional"))
    )
    (net (code "65") (name "Net-(J5-Pad2)") (class "Default")
      (node (ref "J5") (pin "2") (pinfunction "2_2") (pintype "bidirectional"))
      (node (ref "J6") (pin "5") (pinfunction "5_5") (pintype "bidirectional"))
    )
    (net (code "66") (name "Net-(J5-Pad6)") (class "Default")
      (node (ref "J5") (pin "6") (pinfunction "6_6") (pintype "bidirectional"))
      (node (ref "J6") (pin "1") (pinfunction "1_1") (pintype "bidirectional"))
    )
    (net (code "67") (name "Net-(J8-P$2)") (class "Default")
      (node (ref "J8") (pin "2") (pinfunction "P$2_2") (pintype "bidirectional"))
      (node (ref "J9") (pin "7") (pinfunction "P$7_7") (pintype "bidirectional"))
    )
    (net (code "68") (name "Net-(J8-P$3)") (class "Default")
      (node (ref "J8") (pin "3") (pinfunction "P$3_3") (pintype "bidirectional"))
      (node (ref "J9") (pin "6") (pinfunction "P$6_6") (pintype "bidirectional"))
    )
    (net (code "69") (name "Net-(J8-P$4)") (class "Default")
      (node (ref "J8") (pin "4") (pinfunction "P$4_4") (pintype "bidirectional"))
      (node (ref "J9") (pin "5") (pinfunction "P$5_5") (pintype "bidirectional"))
    )
    (net (code "70") (name "Net-(J8-P$5)") (class "Default")
      (node (ref "J8") (pin "5") (pinfunction "P$5_5") (pintype "bidirectional"))
      (node (ref "J9") (pin "4") (pinfunction "P$4_4") (pintype "bidirectional"))
    )
    (net (code "71") (name "Net-(J8-P$6)") (class "Default")
      (node (ref "J8") (pin "6") (pinfunction "P$6_6") (pintype "bidirectional"))
      (node (ref "J9") (pin "3") (pinfunction "P$3_3") (pintype "bidirectional"))
    )
    (net (code "72") (name "Net-(J11-P$1)") (class "Default")
      (node (ref "J11") (pin "1") (pinfunction "P$1_1") (pintype "bidirectional"))
      (node (ref "J12") (pin "8") (pinfunction "P$8_8") (pintype "bidirectional"))
    )
    (net (code "73") (name "Net-(J11-P$3)") (class "Default")
      (node (ref "J11") (pin "3") (pinfunction "P$3_3") (pintype "bidirectional"))
      (node (ref "J12") (pin "6") (pinfunction "P$6_6") (pintype "bidirectional"))
    )
    (net (code "74") (name "Net-(J11-P$4)") (class "Default")
      (node (ref "J11") (pin "4") (pinfunction "P$4_4") (pintype "bidirectional"))
      (node (ref "J12") (pin "5") (pinfunction "P$5_5") (pintype "bidirectional"))
    )
    (net (code "75") (name "Net-(J11-P$5)") (class "Default")
      (node (ref "J11") (pin "5") (pinfunction "P$5_5") (pintype "bidirectional"))
      (node (ref "J12") (pin "4") (pinfunction "P$4_4") (pintype "bidirectional"))
    )
    (net (code "76") (name "Net-(J11-P$6)") (class "Default")
      (node (ref "J11") (pin "6") (pinfunction "P$6_6") (pintype "bidirectional"))
      (node (ref "J12") (pin "3") (pinfunction "P$3_3") (pintype "bidirectional"))
    )
    (net (code "77") (name "Net-(JP-Pad2)") (class "Default")
      (node (ref "JP") (pin "2") (pinfunction "2_2") (pintype "passive"))
      (node (ref "R3") (pin "1") (pinfunction "1_1") (pintype "passive"))
    )
    (net (code "78") (name "Net-(K1-1)") (class "Default")
      (node (ref "K1") (pin "P$1") (pinfunction "1_P$1") (pintype "bidirectional"))
      (node (ref "U2") (pin "2") (pinfunction "PWRKEY_OUT_2") (pintype "output"))
    )
    (net (code "79") (name "Net-(P1-P$1)") (class "Default")
      (node (ref "P1") (pin "1") (pinfunction "P$1_1") (pintype "bidirectional"))
      (node (ref "R11") (pin "1") (pinfunction "1_1") (pintype "passive"))
    )
    (net (code "80") (name "Net-(PWR-Pad-)") (class "Default")
      (node (ref "PWR") (pin "-") (pinfunction "-_-") (pintype "passive"))
      (node (ref "R1") (pin "1") (pinfunction "1_1") (pintype "passive"))
    )
    (net (code "81") (name "Net-(Q1-B)") (class "Default")
      (node (ref "Q1") (pin "1") (pinfunction "B_1") (pintype "passive"))
      (node (ref "R2") (pin "1") (pinfunction "1_1") (pintype "passive"))
      (node (ref "R3") (pin "2") (pinfunction "2_2") (pintype "passive"))
    )
    (net (code "82") (name "Net-(Q3-B)") (class "Default")
      (node (ref "Q3") (pin "1") (pinfunction "B_1") (pintype "passive"))
      (node (ref "R13") (pin "2") (pinfunction "2_2") (pintype "passive"))
      (node (ref "R15") (pin "1") (pinfunction "1_1") (pintype "passive"))
    )
    (net (code "83") (name "Net-(Q3-C)") (class "Default")
      (node (ref "Q3") (pin "3") (pinfunction "C_3") (pintype "passive"))
      (node (ref "R20") (pin "2") (pinfunction "2_2") (pintype "passive"))
    )
    (net (code "84") (name "Net-(Q4-B)") (class "Default")
      (node (ref "Q4") (pin "1") (pinfunction "B_1") (pintype "passive"))
      (node (ref "R14") (pin "2") (pinfunction "2_2") (pintype "passive"))
      (node (ref "R16") (pin "1") (pinfunction "1_1") (pintype "passive"))
    )
    (net (code "85") (name "Net-(Q4-C)") (class "Default")
      (node (ref "Q4") (pin "3") (pinfunction "C_3") (pintype "passive"))
      (node (ref "R21") (pin "2") (pinfunction "2_2") (pintype "passive"))
    )
    (net (code "86") (name "Net-(R8A-2)") (class "Default")
      (node (ref "C9") (pin "2") (pinfunction "2_2") (pintype "passive"))
      (node (ref "D1") (pin "2") (pinfunction "2_2") (pintype "bidirectional"))
      (node (ref "R7") (pin "1") (pinfunction "1_1") (pintype "passive"))
      (node (ref "R8") (pin "7") (pinfunction "2_7") (pintype "passive"))
      (node (ref "R8") (pin "8") (pinfunction "2_8") (pintype "passive"))
      (node (ref "R9") (pin "2") (pinfunction "2_2") (pintype "passive"))
    )
    (net (code "87") (name "Net-(SIMHOLDER-CLK)") (class "Default")
      (node (ref "R18") (pin "1") (pinfunction "1_1") (pintype "passive"))
      (node (ref "SIMHOLDER") (pin "3") (pinfunction "CLK_3") (pintype "bidirectional"))
    )
    (net (code "88") (name "Net-(SIMHOLDER-I{slash}O)") (class "Default")
      (node (ref "R19") (pin "2") (pinfunction "2_2") (pintype "passive"))
      (node (ref "SIMHOLDER") (pin "4") (pinfunction "I/O_4") (pintype "bidirectional"))
    )
    (net (code "89") (name "Net-(SIMHOLDER-RST)") (class "Default")
      (node (ref "R17") (pin "1") (pinfunction "1_1") (pintype "passive"))
      (node (ref "SIMHOLDER") (pin "2") (pinfunction "RST_2") (pintype "bidirectional"))
    )
    (net (code "90") (name "Net-(U1-ADJ)") (class "Default")
      (node (ref "R4") (pin "1") (pinfunction "1_1") (pintype "passive"))
      (node (ref "R6") (pin "2") (pinfunction "2_2") (pintype "passive"))
      (node (ref "U1") (pin "5") (pinfunction "ADJ_5") (pintype "bidirectional"))
    )
    (net (code "91") (name "Net-(U2-MIC_P)") (class "Default")
      (node (ref "C12") (pin "1") (pinfunction "1_1") (pintype "passive"))
      (node (ref "R12") (pin "1") (pinfunction "1_1") (pintype "passive"))
      (node (ref "U2") (pin "19") (pinfunction "MIC_P_19") (pintype "input"))
    )
    (net (code "92") (name "Net-(U2-NETLIGHT)") (class "Default")
      (node (ref "R13") (pin "1") (pinfunction "1_1") (pintype "passive"))
      (node (ref "U2") (pin "52") (pinfunction "NETLIGHT_52") (pintype "output"))
    )
    (net (code "93") (name "Net-(U2-RF_ANT)") (class "Default")
      (node (ref "C10") (pin "2") (pinfunction "2_2") (pintype "passive"))
      (node (ref "R10") (pin "2") (pinfunction "2_2") (pintype "passive"))
      (node (ref "U2") (pin "60") (pinfunction "RF_ANT_60") (pintype "bidirectional"))
    )
    (net (code "94") (name "Net-(U2-SPK_N)") (class "Default")
      (node (ref "C14") (pin "1") (pinfunction "1_1") (pintype "passive"))
      (node (ref "C15") (pin "2") (pinfunction "2_2") (pintype "passive"))
      (node (ref "C18") (pin "1") (pinfunction "1_1") (pintype "passive"))
      (node (ref "C19") (pin "2") (pinfunction "2_2") (pintype "passive"))
      (node (ref "SPK") (pin "R") (pinfunction "R_R") (pintype "bidirectional"))
      (node (ref "U2") (pin "22") (pinfunction "SPK_N_22") (pintype "output"))
    )
    (net (code "95") (name "Net-(U2-SPK_P)") (class "Default")
      (node (ref "C13") (pin "1") (pinfunction "1_1") (pintype "passive"))
      (node (ref "C14") (pin "2") (pinfunction "2_2") (pintype "passive"))
      (node (ref "C17") (pin "1") (pinfunction "1_1") (pintype "passive"))
      (node (ref "C18") (pin "2") (pinfunction "2_2") (pintype "passive"))
      (node (ref "SPK") (pin "L") (pinfunction "L_L") (pintype "bidirectional"))
      (node (ref "U2") (pin "21") (pinfunction "SPK_P_21") (pintype "output"))
    )
    (net (code "96") (name "Net-(U2-STATUS)") (class "Default")
      (node (ref "R14") (pin "1") (pinfunction "1_1") (pintype "passive"))
      (node (ref "U2") (pin "66") (pinfunction "STATUS_66") (pintype "output"))
    )
    (net (code "97") (name "unconnected-(EXT_PWR-PadCDN)") (class "Default")
      (node (ref "EXT_PWR") (pin "CDN") (pinfunction "CDN_CDN") (pintype "bidirectional"))
    )
    (net (code "98") (name "unconnected-(MIC-PadLS)") (class "Default")
      (node (ref "MIC") (pin "LS") (pinfunction "LS_LS") (pintype "bidirectional"))
    )
    (net (code "99") (name "unconnected-(MIC-PadRS)") (class "Default")
      (node (ref "MIC") (pin "RS") (pinfunction "RS_RS") (pintype "bidirectional"))
    )
    (net (code "100") (name "unconnected-(SIMHOLDER-VPP-Pad5)") (class "Default")
      (node (ref "SIMHOLDER") (pin "5") (pinfunction "VPP_5") (pintype "bidirectional"))
    )
    (net (code "101") (name "unconnected-(SPK-PadLS)") (class "Default")
      (node (ref "SPK") (pin "LS") (pinfunction "LS_LS") (pintype "bidirectional"))
    )
    (net (code "102") (name "unconnected-(SPK-PadRS)") (class "Default")
      (node (ref "SPK") (pin "RS") (pinfunction "RS_RS") (pintype "bidirectional"))
    )
    (net (code "103") (name "unconnected-(U2-NRESET-Pad16)") (class "Default")
      (node (ref "U2") (pin "16") (pinfunction "NRESET_16") (pintype "input"))
    )
    (net (code "104") (name "unconnected-(U2-SIM_PRESENCE-Pad34)") (class "Default")
      (node (ref "U2") (pin "34") (pinfunction "SIM_PRESENCE_34") (pintype "input"))
    )
  )
)
